# Adafruit_MCP9808_STEMMA_QT.net
KiCad netlist of a schematic drawn in EAGLE
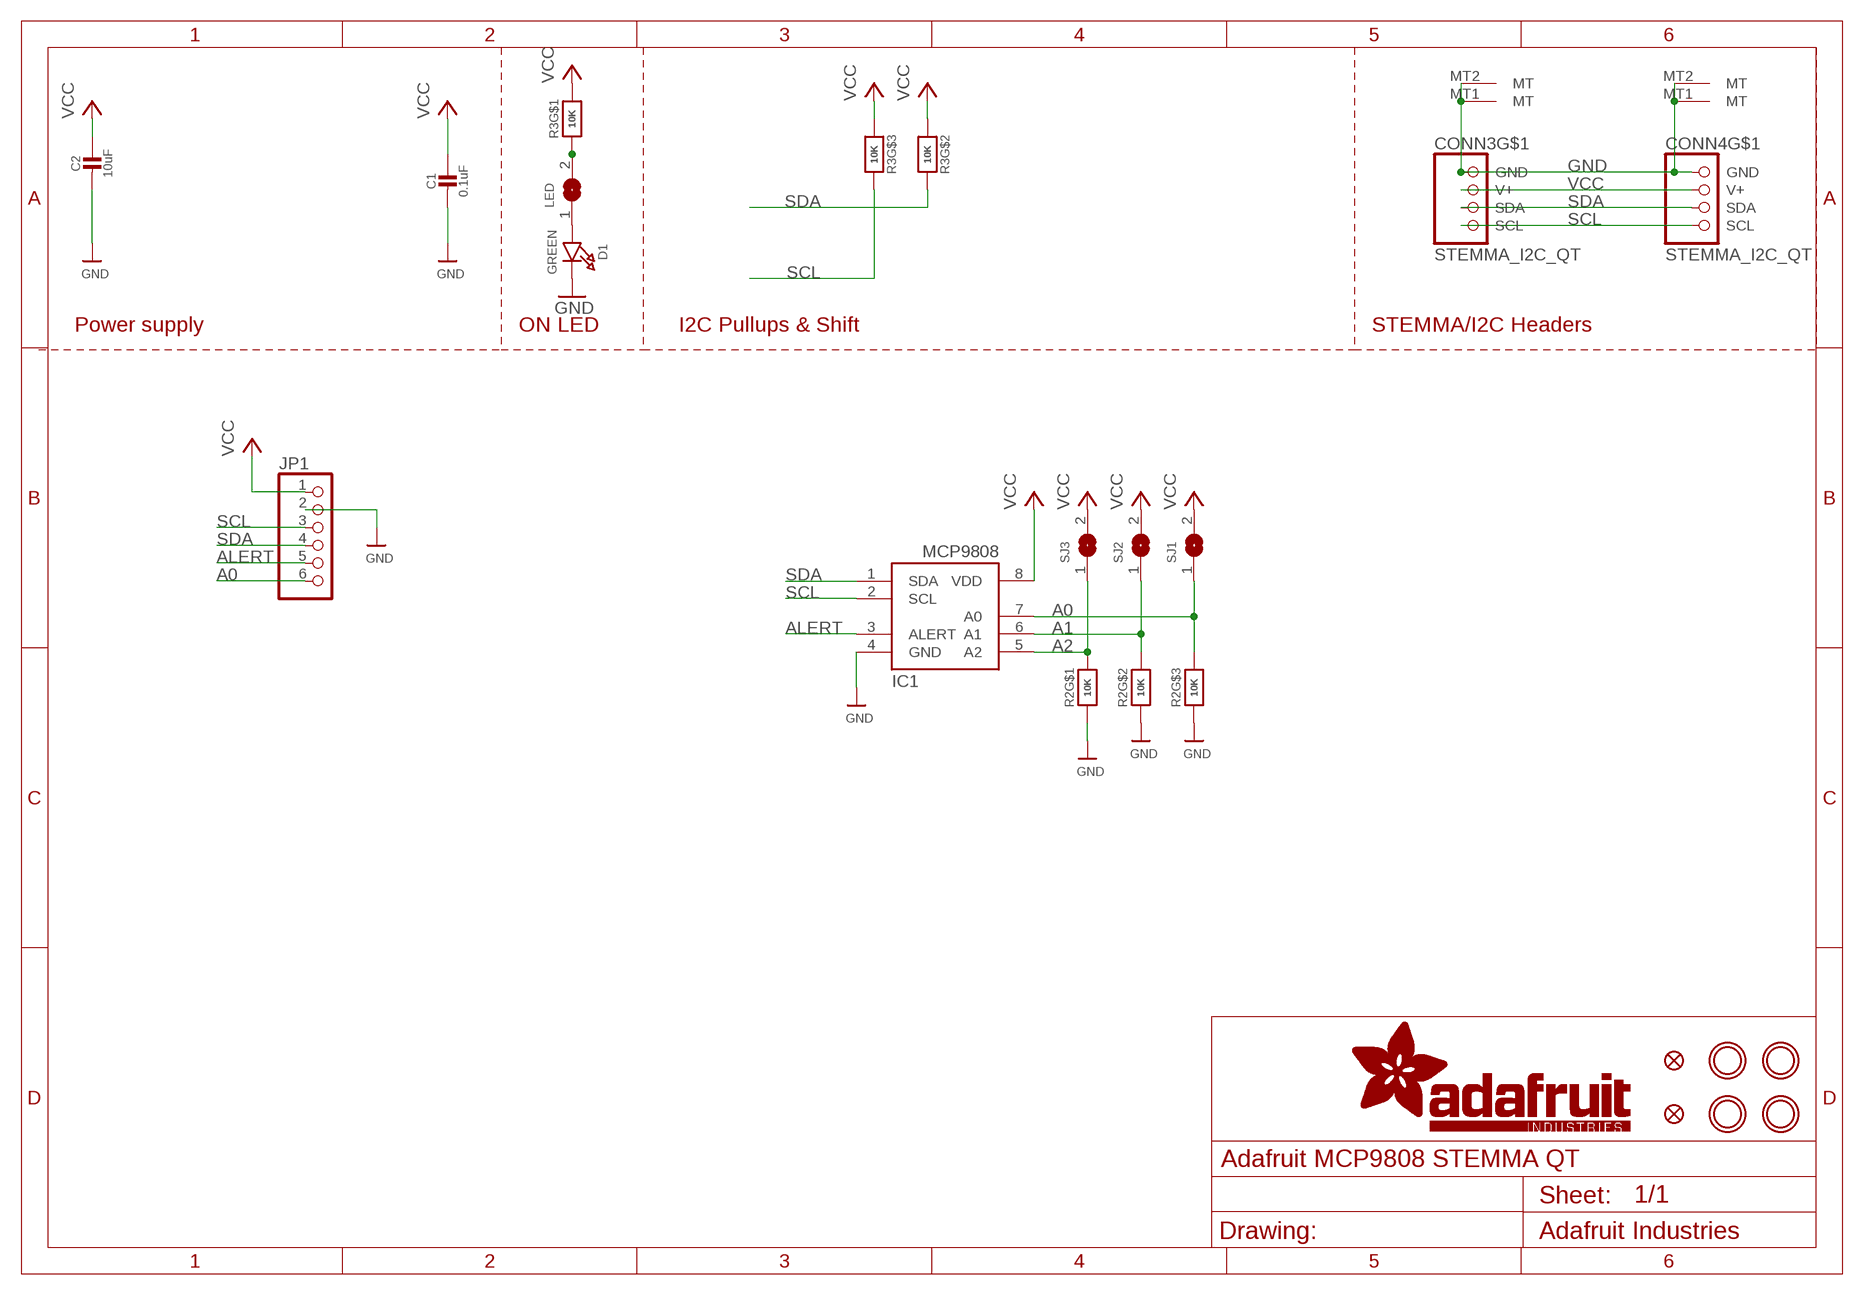
[diagram p0: schematic, sheet 1]

(export (version "E")
  (design (tool "Eeschema 10.0.6"))
  (components
    (comp (ref "C1")
      (value "0.1uF")
      (footprint "eagle-import:0603-NO")
      (libsource (lib "eagle-import") (part "CAP_CERAMIC0603_NO"))
    )
    (comp (ref "C2")
      (value "10uF")
      (footprint "eagle-import:0805-NO")
      (libsource (lib "eagle-import") (part "CAP_CERAMIC0805-NOOUTLINE"))
    )
    (comp (ref "CONN3")
      (value "STEMMA_I2C_QT")
      (footprint "eagle-import:JST_SH4")
      (libsource (lib "eagle-import") (part "STEMMA_I2C_QT"))
    )
    (comp (ref "CONN4")
      (value "STEMMA_I2C_QT")
      (footprint "eagle-import:JST_SH4")
      (libsource (lib "eagle-import") (part "STEMMA_I2C_QT"))
    )
    (comp (ref "D1")
      (value "GREEN")
      (footprint "eagle-import:CHIPLED_0603_NOOUTLINE")
      (libsource (lib "eagle-import") (part "LED0603_NOOUTLINE"))
    )
    (comp (ref "FID3")
      (value "FIDUCIAL_1MM")
      (footprint "eagle-import:FIDUCIAL_1MM")
      (libsource (lib "eagle-import") (part "FIDUCIAL_1MM"))
    )
    (comp (ref "FID4")
      (value "FIDUCIAL_1MM")
      (footprint "eagle-import:FIDUCIAL_1MM")
      (libsource (lib "eagle-import") (part "FIDUCIAL_1MM"))
    )
    (comp (ref "IC1")
      (value "MCP9808-E/MS")
      (footprint "eagle-import:MSOP8_0.65MM")
      (libsource (lib "eagle-import") (part "MCP9808-E/MS"))
    )
    (comp (ref "JP1")
      (value "HEADER-1X670MIL")
      (footprint "eagle-import:1X06_ROUND_70")
      (libsource (lib "eagle-import") (part "HEADER-1X670MIL"))
    )
    (comp (ref "LED")
      (value "SOLDERJUMPERCLOSED")
      (footprint "eagle-import:SOLDERJUMPER_CLOSEDWIRE")
      (libsource (lib "eagle-import") (part "SOLDERJUMPERCLOSED"))
    )
    (comp (ref "R2")
      (value "10K")
      (footprint "eagle-import:RESPACK_4X0603")
      (libsource (lib "eagle-import") (part "RESISTOR_4PACK"))
    )
    (comp (ref "R3")
      (value "10K")
      (footprint "eagle-import:RESPACK_4X0603")
      (libsource (lib "eagle-import") (part "RESISTOR_4PACK"))
    )
    (comp (ref "SJ1")
      (value "SOLDERJUMPER")
      (footprint "eagle-import:SOLDERJUMPER_ARROW_NOPASTE")
      (libsource (lib "eagle-import") (part "SOLDERJUMPER"))
    )
    (comp (ref "SJ2")
      (value "SOLDERJUMPER")
      (footprint "eagle-import:SOLDERJUMPER_ARROW_NOPASTE")
      (libsource (lib "eagle-import") (part "SOLDERJUMPER"))
    )
    (comp (ref "SJ3")
      (value "SOLDERJUMPER")
      (footprint "eagle-import:SOLDERJUMPER_ARROW_NOPASTE")
      (libsource (lib "eagle-import") (part "SOLDERJUMPER"))
    )
    (comp (ref "U$1")
      (value "MOUNTINGHOLE2.5")
      (footprint "eagle-import:MOUNTINGHOLE_2.5_PLATED")
      (libsource (lib "eagle-import") (part "MOUNTINGHOLE2.5"))
    )
    (comp (ref "U$17")
      (value "MOUNTINGHOLE2.5")
      (footprint "eagle-import:MOUNTINGHOLE_2.5_PLATED")
      (libsource (lib "eagle-import") (part "MOUNTINGHOLE2.5"))
    )
    (comp (ref "U$19")
      (value "MOUNTINGHOLE2.5")
      (footprint "eagle-import:MOUNTINGHOLE_2.5_PLATED")
      (libsource (lib "eagle-import") (part "MOUNTINGHOLE2.5"))
    )
    (comp (ref "U$21")
      (value "MOUNTINGHOLE2.5")
      (footprint "eagle-import:MOUNTINGHOLE_2.5_PLATED")
      (libsource (lib "eagle-import") (part "MOUNTINGHOLE2.5"))
    )
  )
  (nets
    (net (code "1") (name "/A0") (class "Default")
      (node (ref "IC1") (pin "7") (pinfunction "A0_7") (pintype "input"))
      (node (ref "JP1") (pin "6") (pinfunction "6_6") (pintype "passive"))
      (node (ref "R2") (pin "6") (pinfunction "2_6") (pintype "passive"))
      (node (ref "SJ1") (pin "1") (pinfunction "1_1") (pintype "passive"))
    )
    (net (code "2") (name "/A1") (class "Default")
      (node (ref "IC1") (pin "6") (pinfunction "A1_6") (pintype "input"))
      (node (ref "R2") (pin "7") (pinfunction "2_7") (pintype "passive"))
      (node (ref "SJ2") (pin "1") (pinfunction "1_1") (pintype "passive"))
    )
    (net (code "3") (name "/A2") (class "Default")
      (node (ref "IC1") (pin "5") (pinfunction "A2_5") (pintype "input"))
      (node (ref "R2") (pin "8") (pinfunction "2_8") (pintype "passive"))
      (node (ref "SJ3") (pin "1") (pinfunction "1_1") (pintype "passive"))
    )
    (net (code "4") (name "/ALERT") (class "Default")
      (node (ref "IC1") (pin "3") (pinfunction "ALERT_3") (pintype "open_collector"))
      (node (ref "JP1") (pin "5") (pinfunction "5_5") (pintype "passive"))
    )
    (net (code "5") (name "/SCL") (class "Default")
      (node (ref "CONN3") (pin "4") (pinfunction "SCL_4") (pintype "passive"))
      (node (ref "CONN4") (pin "4") (pinfunction "SCL_4") (pintype "passive"))
      (node (ref "IC1") (pin "2") (pinfunction "SCL_2") (pintype "bidirectional"))
      (node (ref "JP1") (pin "3") (pinfunction "3_3") (pintype "passive"))
      (node (ref "R3") (pin "6") (pinfunction "2_6") (pintype "passive"))
    )
    (net (code "6") (name "/SDA") (class "Default")
      (node (ref "CONN3") (pin "3") (pinfunction "SDA_3") (pintype "passive"))
      (node (ref "CONN4") (pin "3") (pinfunction "SDA_3") (pintype "passive"))
      (node (ref "IC1") (pin "1") (pinfunction "SDA_1") (pintype "bidirectional"))
      (node (ref "JP1") (pin "4") (pinfunction "4_4") (pintype "passive"))
      (node (ref "R3") (pin "7") (pinfunction "2_7") (pintype "passive"))
    )
    (net (code "7") (name "GND") (class "Default")
      (node (ref "C1") (pin "2") (pinfunction "2_2") (pintype "passive"))
      (node (ref "C2") (pin "2") (pinfunction "2_2") (pintype "passive"))
      (node (ref "CONN3") (pin "1") (pinfunction "GND_1") (pintype "passive"))
      (node (ref "CONN3") (pin "MT1") (pinfunction "MT_MT1") (pintype "bidirectional"))
      (node (ref "CONN3") (pin "MT2") (pinfunction "MT_MT2") (pintype "bidirectional"))
      (node (ref "CONN4") (pin "1") (pinfunction "GND_1") (pintype "passive"))
      (node (ref "CONN4") (pin "MT1") (pinfunction "MT_MT1") (pintype "bidirectional"))
      (node (ref "CONN4") (pin "MT2") (pinfunction "MT_MT2") (pintype "bidirectional"))
      (node (ref "D1") (pin "C") (pinfunction "C_C") (pintype "passive"))
      (node (ref "IC1") (pin "4") (pinfunction "GND_4") (pintype "power_in"))
      (node (ref "JP1") (pin "2") (pinfunction "2_2") (pintype "passive"))
      (node (ref "R2") (pin "1") (pinfunction "1_1") (pintype "passive"))
      (node (ref "R2") (pin "2") (pinfunction "1_2") (pintype "passive"))
      (node (ref "R2") (pin "3") (pinfunction "1_3") (pintype "passive"))
    )
    (net (code "8") (name "Net-(D1-PadA)") (class "Default")
      (node (ref "D1") (pin "A") (pinfunction "A_A") (pintype "passive"))
      (node (ref "LED") (pin "1") (pinfunction "1_1") (pintype "passive"))
    )
    (net (code "9") (name "Net-(LED-Pad2)") (class "Default")
      (node (ref "LED") (pin "2") (pinfunction "2_2") (pintype "passive"))
      (node (ref "R3") (pin "1") (pinfunction "1_1") (pintype "passive"))
    )
    (net (code "10") (name "VCC") (class "Default")
      (node (ref "C1") (pin "1") (pinfunction "1_1") (pintype "passive"))
      (node (ref "C2") (pin "1") (pinfunction "1_1") (pintype "passive"))
      (node (ref "CONN3") (pin "2") (pinfunction "V+_2") (pintype "passive"))
      (node (ref "CONN4") (pin "2") (pinfunction "V+_2") (pintype "passive"))
      (node (ref "IC1") (pin "8") (pinfunction "VDD_8") (pintype "power_in"))
      (node (ref "JP1") (pin "1") (pinfunction "1_1") (pintype "passive"))
      (node (ref "R3") (pin "2") (pinfunction "1_2") (pintype "passive"))
      (node (ref "R3") (pin "3") (pinfunction "1_3") (pintype "passive"))
      (node (ref "R3") (pin "8") (pinfunction "2_8") (pintype "passive"))
      (node (ref "SJ1") (pin "2") (pinfunction "2_2") (pintype "passive"))
      (node (ref "SJ2") (pin "2") (pinfunction "2_2") (pintype "passive"))
      (node (ref "SJ3") (pin "2") (pinfunction "2_2") (pintype "passive"))
    )
  )
)
